# mikroAmpMeterV150_AnalogFrontend.net
KiCad netlist of a schematic drawn in EAGLE
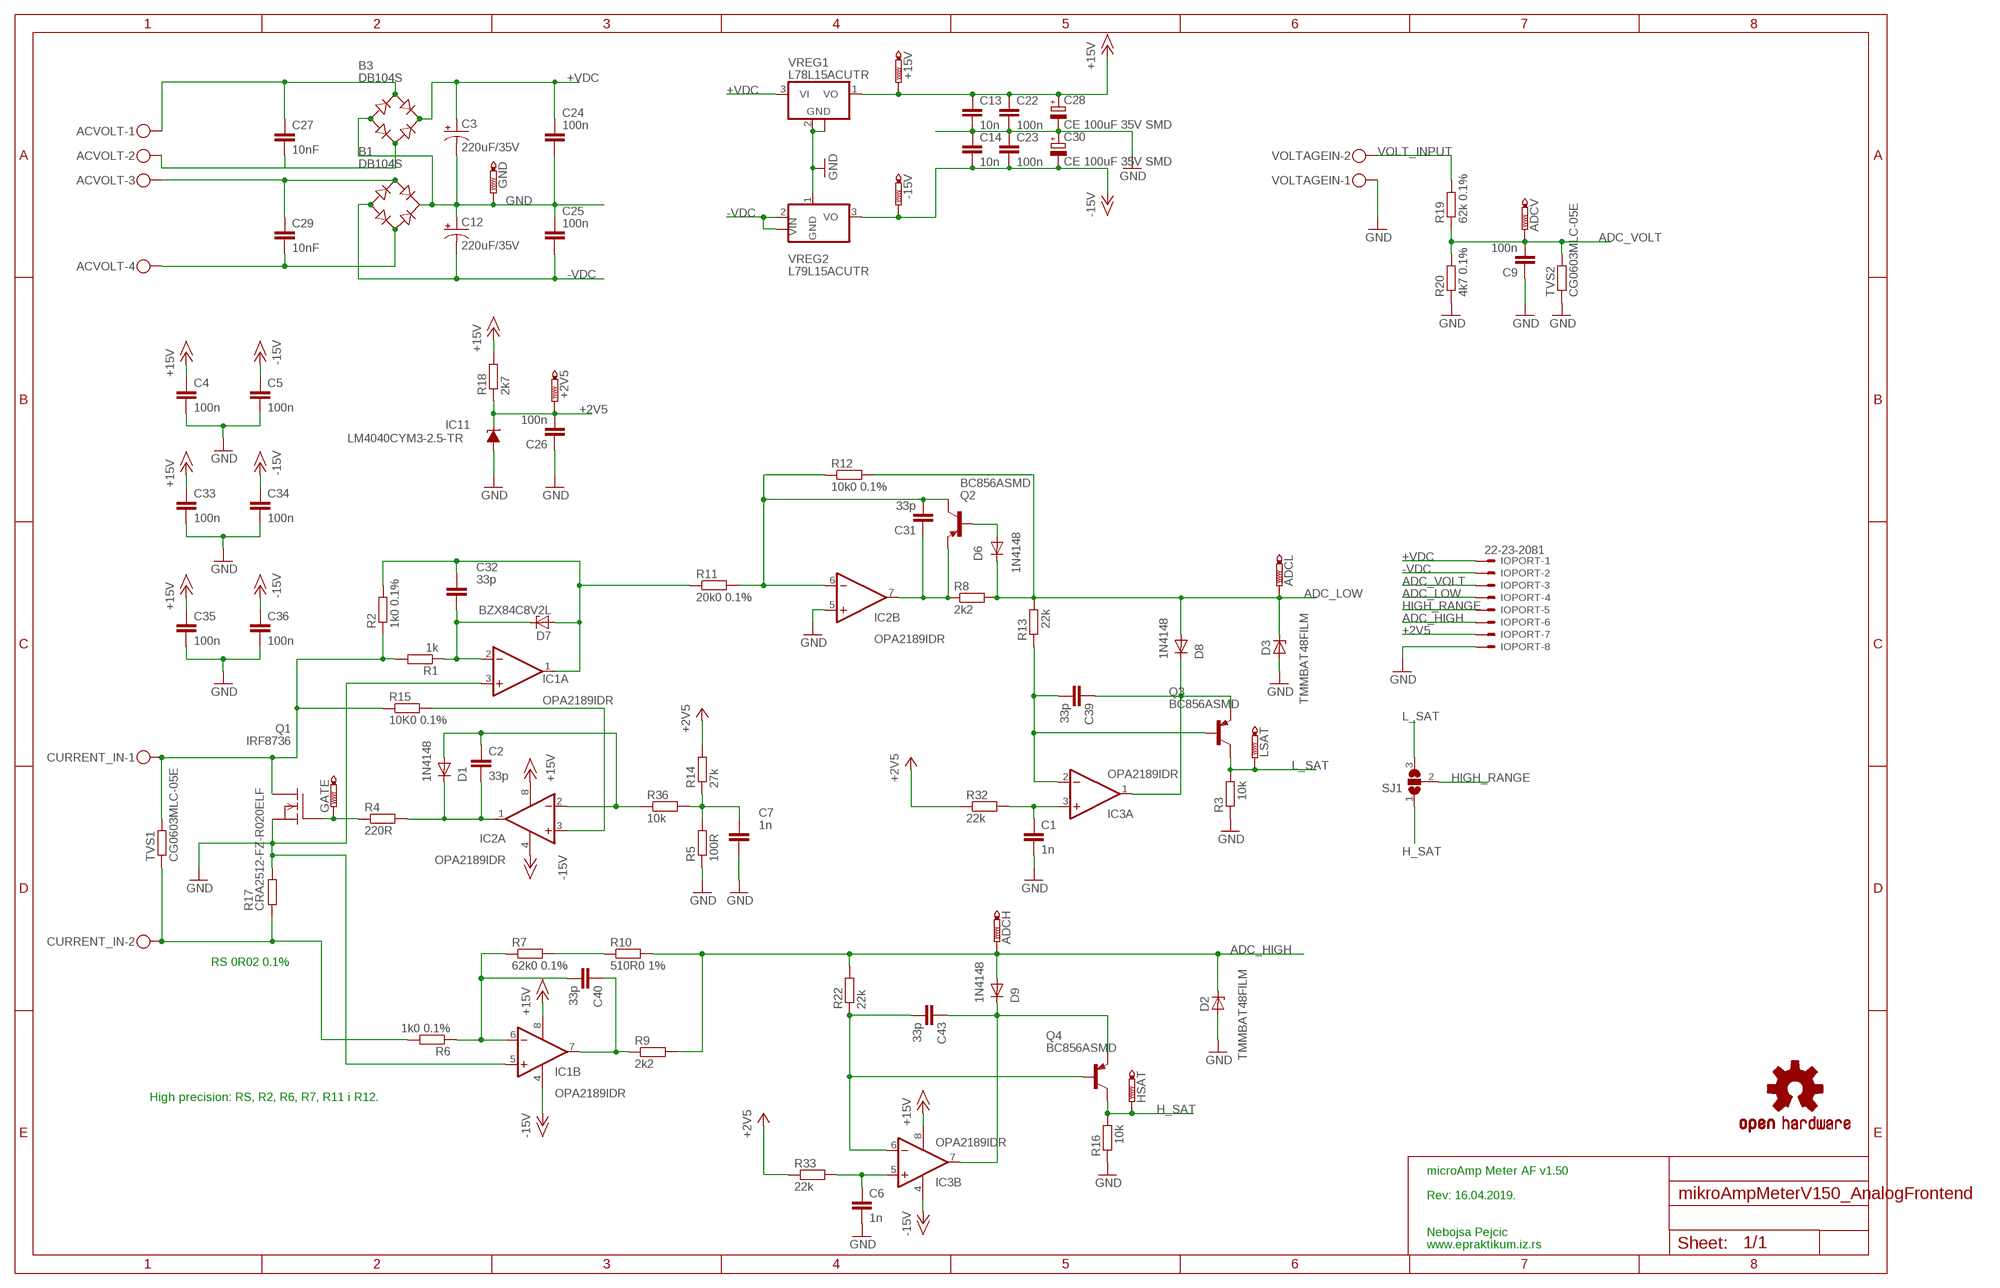
[diagram p0: schematic, sheet 1]

(export (version "E")
  (design (tool "Eeschema 10.0.6"))
  (components
    (comp (ref "+2V5")
      (value "PTR1TP15R")
      (footprint "eagle-import:TP15R")
      (libsource (lib "eagle-import") (part "PTR1TP15R"))
    )
    (comp (ref "+15V")
      (value "PTR1TP15R")
      (footprint "eagle-import:TP15R")
      (libsource (lib "eagle-import") (part "PTR1TP15R"))
    )
    (comp (ref "-15V")
      (value "PTR1TP15R")
      (footprint "eagle-import:TP15R")
      (libsource (lib "eagle-import") (part "PTR1TP15R"))
    )
    (comp (ref "ACVOLT")
      (value "MKDSN1,5/4-5,08")
      (footprint "eagle-import:MKDSN1,5_4-5,08")
      (fields (field (name "MPN") "SMKDSN1,5/4-5,08"))
      (libsource (lib "eagle-import") (part "MKDSN1,5/4-5,08"))
    )
    (comp (ref "ADCH")
      (value "PTR1TP15R")
      (footprint "eagle-import:TP15R")
      (libsource (lib "eagle-import") (part "PTR1TP15R"))
    )
    (comp (ref "ADCL")
      (value "PTR1TP15R")
      (footprint "eagle-import:TP15R")
      (libsource (lib "eagle-import") (part "PTR1TP15R"))
    )
    (comp (ref "ADCV")
      (value "PTR1TP15R")
      (footprint "eagle-import:TP15R")
      (libsource (lib "eagle-import") (part "PTR1TP15R"))
    )
    (comp (ref "B1")
      (value "DB104S")
      (footprint "eagle-import:DBS")
      (libsource (lib "eagle-import") (part "DB?GLS204"))
    )
    (comp (ref "B3")
      (value "DB104S")
      (footprint "eagle-import:DBS")
      (libsource (lib "eagle-import") (part "DB?GLS204"))
    )
    (comp (ref "C1")
      (value "1n")
      (footprint "eagle-import:C0805")
      (libsource (lib "eagle-import") (part "C-EUC0805"))
    )
    (comp (ref "C2")
      (value "33p")
      (footprint "eagle-import:C0805")
      (libsource (lib "eagle-import") (part "C-EUC0805"))
    )
    (comp (ref "C3")
      (value "220uF/35V")
      (footprint "eagle-import:153CLV-1014")
      (libsource (lib "eagle-import") (part "CPOL-US153CLV-1014"))
    )
    (comp (ref "C4")
      (value "100n")
      (footprint "eagle-import:C0805")
      (libsource (lib "eagle-import") (part "C-EUC0805"))
    )
    (comp (ref "C5")
      (value "100n")
      (footprint "eagle-import:C0805")
      (libsource (lib "eagle-import") (part "C-EUC0805"))
    )
    (comp (ref "C6")
      (value "1n")
      (footprint "eagle-import:C0805")
      (libsource (lib "eagle-import") (part "C-EUC0805"))
    )
    (comp (ref "C7")
      (value "1n")
      (footprint "eagle-import:C0805")
      (libsource (lib "eagle-import") (part "C-EUC0805"))
    )
    (comp (ref "C9")
      (value "100n")
      (footprint "eagle-import:C0805")
      (libsource (lib "eagle-import") (part "C-EUC0805"))
    )
    (comp (ref "C12")
      (value "220uF/35V")
      (footprint "eagle-import:153CLV-1014")
      (libsource (lib "eagle-import") (part "CPOL-US153CLV-1014"))
    )
    (comp (ref "C13")
      (value "10n")
      (footprint "eagle-import:C0805")
      (libsource (lib "eagle-import") (part "C-EUC0805"))
    )
    (comp (ref "C14")
      (value "10n")
      (footprint "eagle-import:C0805")
      (libsource (lib "eagle-import") (part "C-EUC0805"))
    )
    (comp (ref "C22")
      (value "100n")
      (footprint "eagle-import:C0805")
      (libsource (lib "eagle-import") (part "C-EUC0805"))
    )
    (comp (ref "C23")
      (value "100n")
      (footprint "eagle-import:C0805")
      (libsource (lib "eagle-import") (part "C-EUC0805"))
    )
    (comp (ref "C24")
      (value "100n")
      (footprint "eagle-import:C0805")
      (libsource (lib "eagle-import") (part "C-EUC0805"))
    )
    (comp (ref "C25")
      (value "100n")
      (footprint "eagle-import:C0805")
      (libsource (lib "eagle-import") (part "C-EUC0805"))
    )
    (comp (ref "C26")
      (value "100n")
      (footprint "eagle-import:C0805")
      (libsource (lib "eagle-import") (part "C-EUC0805"))
    )
    (comp (ref "C27")
      (value "10nF")
      (footprint "eagle-import:C1206")
      (libsource (lib "eagle-import") (part "C-EUC1206"))
    )
    (comp (ref "C28")
      (value "CE 100uF 35V SMD")
      (footprint "eagle-import:UD-6,3X7,7_NICHICON")
      (libsource (lib "eagle-import") (part "CPOL-EUUD-6,3X7,7"))
    )
    (comp (ref "C29")
      (value "10nF")
      (footprint "eagle-import:C1206")
      (libsource (lib "eagle-import") (part "C-EUC1206"))
    )
    (comp (ref "C30")
      (value "CE 100uF 35V SMD")
      (footprint "eagle-import:UD-6,3X7,7_NICHICON")
      (libsource (lib "eagle-import") (part "CPOL-EUUD-6,3X7,7"))
    )
    (comp (ref "C31")
      (value "33p")
      (footprint "eagle-import:C0805")
      (libsource (lib "eagle-import") (part "C-EUC0805"))
    )
    (comp (ref "C32")
      (value "33p")
      (footprint "eagle-import:C0805")
      (libsource (lib "eagle-import") (part "C-EUC0805"))
    )
    (comp (ref "C33")
      (value "100n")
      (footprint "eagle-import:C0805")
      (libsource (lib "eagle-import") (part "C-EUC0805"))
    )
    (comp (ref "C34")
      (value "100n")
      (footprint "eagle-import:C0805")
      (libsource (lib "eagle-import") (part "C-EUC0805"))
    )
    (comp (ref "C35")
      (value "100n")
      (footprint "eagle-import:C0805")
      (libsource (lib "eagle-import") (part "C-EUC0805"))
    )
    (comp (ref "C36")
      (value "100n")
      (footprint "eagle-import:C0805")
      (libsource (lib "eagle-import") (part "C-EUC0805"))
    )
    (comp (ref "C39")
      (value "33p")
      (footprint "eagle-import:C0805")
      (libsource (lib "eagle-import") (part "C-EUC0805"))
    )
    (comp (ref "C40")
      (value "33p")
      (footprint "eagle-import:C0805")
      (libsource (lib "eagle-import") (part "C-EUC0805"))
    )
    (comp (ref "C43")
      (value "33p")
      (footprint "eagle-import:C0805")
      (libsource (lib "eagle-import") (part "C-EUC0805"))
    )
    (comp (ref "CURRENT_IN")
      (value "MKDSN1,5/2-5,08")
      (footprint "eagle-import:MKDSN1,5_2-5,08")
      (fields (field (name "MPN") "MKDSN 1,5/2-5.08"))
      (libsource (lib "eagle-import") (part "MKDSN1,5/2-5,08"))
    )
    (comp (ref "D1")
      (value "1N4148")
      (footprint "eagle-import:SOD80C")
      (libsource (lib "eagle-import") (part "DIODE-SOD80C"))
    )
    (comp (ref "D2")
      (value "TMMBAT48FILM")
      (footprint "eagle-import:SOD80C")
      (libsource (lib "eagle-import") (part "ZENER-DIODESOD80C"))
    )
    (comp (ref "D3")
      (value "TMMBAT48FILM")
      (footprint "eagle-import:SOD80C")
      (libsource (lib "eagle-import") (part "ZENER-DIODESOD80C"))
    )
    (comp (ref "D6")
      (value "1N4148")
      (footprint "eagle-import:SOD80C")
      (libsource (lib "eagle-import") (part "DIODE-SOD80C"))
    )
    (comp (ref "D7")
      (value "BZX84C8V2L")
      (footprint "eagle-import:SOD80C")
      (libsource (lib "eagle-import") (part "ZENER-DIODESOD80C"))
    )
    (comp (ref "D8")
      (value "1N4148")
      (footprint "eagle-import:SOD80C")
      (libsource (lib "eagle-import") (part "DIODE-SOD80C"))
    )
    (comp (ref "D9")
      (value "1N4148")
      (footprint "eagle-import:SOD80C")
      (libsource (lib "eagle-import") (part "DIODE-SOD80C"))
    )
    (comp (ref "GATE")
      (value "PTR1TP15R")
      (footprint "eagle-import:TP15R")
      (libsource (lib "eagle-import") (part "PTR1TP15R"))
    )
    (comp (ref "GND")
      (value "PTR1TP15R")
      (footprint "eagle-import:TP15R")
      (libsource (lib "eagle-import") (part "PTR1TP15R"))
    )
    (comp (ref "HSAT")
      (value "PTR1TP15R")
      (footprint "eagle-import:TP15R")
      (libsource (lib "eagle-import") (part "PTR1TP15R"))
    )
    (comp (ref "IC1")
      (value "OPA2189IDR")
      (footprint "eagle-import:SO08@1")
      (libsource (lib "eagle-import") (part "OPA222D7"))
    )
    (comp (ref "IC2")
      (value "OPA2189IDR")
      (footprint "eagle-import:SO08@1")
      (libsource (lib "eagle-import") (part "OPA222D7"))
    )
    (comp (ref "IC3")
      (value "OPA2189IDR")
      (footprint "eagle-import:SO08@1")
      (libsource (lib "eagle-import") (part "OPA222D7"))
    )
    (comp (ref "IC11")
      (value "LM4040CYM3-2.5-TR")
      (footprint "eagle-import:DBZ_R-PDSO-G3")
      (fields (field (name "MPN") "LM4041A12IDBZR"))
      (libsource (lib "eagle-import") (part "LM4041DBZA12"))
    )
    (comp (ref "IOPORT")
      (value "22-23-2081")
      (footprint "eagle-import:22-23-2081")
      (fields (field (name "MF") "MOLEX"))
      (libsource (lib "eagle-import") (part "22-23-2081"))
    )
    (comp (ref "LOGO1")
      (value "OSHW-LOGOM")
      (footprint "eagle-import:OSHW-LOGO-M")
      (libsource (lib "eagle-import") (part "OSHW-LOGOM"))
    )
    (comp (ref "LSAT")
      (value "PTR1TP15R")
      (footprint "eagle-import:TP15R")
      (libsource (lib "eagle-import") (part "PTR1TP15R"))
    )
    (comp (ref "Q1")
      (value "IRF8736")
      (footprint "eagle-import:SO-8")
      (libsource (lib "eagle-import") (part "FDS5680"))
    )
    (comp (ref "Q2")
      (value "BC856ASMD")
      (footprint "eagle-import:SOT23-BEC")
      (libsource (lib "eagle-import") (part "BC856SMDA"))
    )
    (comp (ref "Q3")
      (value "BC856ASMD")
      (footprint "eagle-import:SOT23-BEC")
      (libsource (lib "eagle-import") (part "BC856SMDA"))
    )
    (comp (ref "Q4")
      (value "BC856ASMD")
      (footprint "eagle-import:SOT23-BEC")
      (libsource (lib "eagle-import") (part "BC856SMDA"))
    )
    (comp (ref "R1")
      (value "1k")
      (footprint "eagle-import:R0805")
      (libsource (lib "eagle-import") (part "R-EU_R0805"))
    )
    (comp (ref "R2")
      (value "1k0 0.1%")
      (footprint "eagle-import:R0805")
      (libsource (lib "eagle-import") (part "R-EU_R0805"))
    )
    (comp (ref "R3")
      (value "10k")
      (footprint "eagle-import:R0805")
      (libsource (lib "eagle-import") (part "R-EU_R0805"))
    )
    (comp (ref "R4")
      (value "220R")
      (footprint "eagle-import:R0805")
      (libsource (lib "eagle-import") (part "R-EU_R0805"))
    )
    (comp (ref "R5")
      (value "100R")
      (footprint "eagle-import:R0805")
      (libsource (lib "eagle-import") (part "R-EU_R0805"))
    )
    (comp (ref "R6")
      (value "1k0 0.1%")
      (footprint "eagle-import:R0805")
      (libsource (lib "eagle-import") (part "R-EU_R0805"))
    )
    (comp (ref "R7")
      (value "62k0 0.1%")
      (footprint "eagle-import:R0805")
      (libsource (lib "eagle-import") (part "R-EU_R0805"))
    )
    (comp (ref "R8")
      (value "2k2")
      (footprint "eagle-import:R0805")
      (libsource (lib "eagle-import") (part "R-EU_R0805"))
    )
    (comp (ref "R9")
      (value "2k2")
      (footprint "eagle-import:R0805")
      (libsource (lib "eagle-import") (part "R-EU_R0805"))
    )
    (comp (ref "R10")
      (value "510R0 1%")
      (footprint "eagle-import:R0805")
      (libsource (lib "eagle-import") (part "R-EU_R0805"))
    )
    (comp (ref "R11")
      (value "20k0 0.1%")
      (footprint "eagle-import:R0805")
      (libsource (lib "eagle-import") (part "R-EU_R0805"))
    )
    (comp (ref "R12")
      (value "10k0 0.1%")
      (footprint "eagle-import:R0805")
      (libsource (lib "eagle-import") (part "R-EU_R0805"))
    )
    (comp (ref "R13")
      (value "22k")
      (footprint "eagle-import:R0805")
      (libsource (lib "eagle-import") (part "R-EU_R0805"))
    )
    (comp (ref "R14")
      (value "27k")
      (footprint "eagle-import:R0805")
      (libsource (lib "eagle-import") (part "R-EU_R0805"))
    )
    (comp (ref "R15")
      (value "10K0 0.1%")
      (footprint "eagle-import:R0805")
      (libsource (lib "eagle-import") (part "R-EU_R0805"))
    )
    (comp (ref "R16")
      (value "10k")
      (footprint "eagle-import:R0805")
      (libsource (lib "eagle-import") (part "R-EU_R0805"))
    )
    (comp (ref "R17")
      (value "CRA2512-FZ-R020ELF")
      (footprint "eagle-import:R2512")
      (libsource (lib "eagle-import") (part "R-EU_R2512"))
    )
    (comp (ref "R18")
      (value "2k7")
      (footprint "eagle-import:R0805")
      (libsource (lib "eagle-import") (part "R-EU_R0805"))
    )
    (comp (ref "R19")
      (value "62k 0.1%")
      (footprint "eagle-import:R0805")
      (libsource (lib "eagle-import") (part "R-EU_R0805"))
    )
    (comp (ref "R20")
      (value "4k7 0.1%")
      (footprint "eagle-import:R0805")
      (libsource (lib "eagle-import") (part "R-EU_R0805"))
    )
    (comp (ref "R22")
      (value "22k")
      (footprint "eagle-import:R0805")
      (libsource (lib "eagle-import") (part "R-EU_R0805"))
    )
    (comp (ref "R32")
      (value "22k")
      (footprint "eagle-import:R0805")
      (libsource (lib "eagle-import") (part "R-EU_R0805"))
    )
    (comp (ref "R33")
      (value "22k")
      (footprint "eagle-import:R0805")
      (libsource (lib "eagle-import") (part "R-EU_R0805"))
    )
    (comp (ref "R36")
      (value "10k")
      (footprint "eagle-import:R0805")
      (libsource (lib "eagle-import") (part "R-EU_R0805"))
    )
    (comp (ref "SJ1")
      (value "SJ2W")
      (footprint "eagle-import:SJ_2")
      (libsource (lib "eagle-import") (part "SJ2W"))
    )
    (comp (ref "TVS1")
      (value "CG0603MLC-05E")
      (footprint "eagle-import:R0805")
      (libsource (lib "eagle-import") (part "R-EU_R0805"))
    )
    (comp (ref "TVS2")
      (value "CG0603MLC-05E")
      (footprint "eagle-import:R0805")
      (libsource (lib "eagle-import") (part "R-EU_R0805"))
    )
    (comp (ref "VOLTAGEIN")
      (value "MKDSN1,5/2-5,08")
      (footprint "eagle-import:MKDSN1,5_2-5,08")
      (fields
        (field (name "MPN") "MKDSN 1,5/2-5.08")
        (field (name "MPN_1") "MKDSN 1,5/2-5.08")
        (field (name "OC_FARNELL") "1792903")
        (field (name "OC_NEWARK") "30M2397")
      )
      (libsource (lib "eagle-import") (part "MKDSN1,5/2-5,08"))
    )
    (comp (ref "VREG1")
      (value "L78L15ACUTR")
      (footprint "eagle-import:SOT89")
      (libsource (lib "eagle-import") (part "78LF05"))
    )
    (comp (ref "VREG2")
      (value "L79L15ACUTR")
      (footprint "eagle-import:SOT89")
      (libsource (lib "eagle-import") (part "L79L15ACUTR"))
    )
  )
  (nets
    (net (code "1") (name "+2V5") (class "Default")
      (node (ref "+2V5") (pin "TP") (pinfunction "TP_TP") (pintype "input"))
      (node (ref "C26") (pin "2") (pinfunction "2_2") (pintype "passive"))
      (node (ref "IC11") (pin "1") (pinfunction "C_1") (pintype "passive"))
      (node (ref "IOPORT") (pin "7") (pinfunction "S_7") (pintype "passive"))
      (node (ref "R14") (pin "2") (pinfunction "2_2") (pintype "passive"))
      (node (ref "R18") (pin "1") (pinfunction "1_1") (pintype "passive"))
      (node (ref "R32") (pin "1") (pinfunction "1_1") (pintype "passive"))
      (node (ref "R33") (pin "1") (pinfunction "1_1") (pintype "passive"))
    )
    (net (code "2") (name "+15V") (class "Default")
      (node (ref "+15V") (pin "TP") (pinfunction "TP_TP") (pintype "input"))
      (node (ref "C13") (pin "1") (pinfunction "1_1") (pintype "passive"))
      (node (ref "C22") (pin "1") (pinfunction "1_1") (pintype "passive"))
      (node (ref "C28") (pin "+") (pinfunction "+_+") (pintype "passive"))
      (node (ref "C33") (pin "1") (pinfunction "1_1") (pintype "passive"))
      (node (ref "C35") (pin "1") (pinfunction "1_1") (pintype "passive"))
      (node (ref "C4") (pin "1") (pinfunction "1_1") (pintype "passive"))
      (node (ref "IC1") (pin "8") (pinfunction "V+_8") (pintype "power_in"))
      (node (ref "IC2") (pin "8") (pinfunction "V+_8") (pintype "power_in"))
      (node (ref "IC3") (pin "8") (pinfunction "V+_8") (pintype "power_in"))
      (node (ref "R18") (pin "2") (pinfunction "2_2") (pintype "passive"))
      (node (ref "VREG1") (pin "1") (pinfunction "VO_1") (pintype "passive"))
    )
    (net (code "3") (name "-15V") (class "Default")
      (node (ref "-15V") (pin "TP") (pinfunction "TP_TP") (pintype "input"))
      (node (ref "C14") (pin "2") (pinfunction "2_2") (pintype "passive"))
      (node (ref "C23") (pin "2") (pinfunction "2_2") (pintype "passive"))
      (node (ref "C30") (pin "-") (pinfunction "-_-") (pintype "passive"))
      (node (ref "C34") (pin "1") (pinfunction "1_1") (pintype "passive"))
      (node (ref "C36") (pin "1") (pinfunction "1_1") (pintype "passive"))
      (node (ref "C5") (pin "1") (pinfunction "1_1") (pintype "passive"))
      (node (ref "IC1") (pin "4") (pinfunction "V-_4") (pintype "power_in"))
      (node (ref "IC2") (pin "4") (pinfunction "V-_4") (pintype "power_in"))
      (node (ref "IC3") (pin "4") (pinfunction "V-_4") (pintype "power_in"))
      (node (ref "VREG2") (pin "3") (pinfunction "VO_3") (pintype "passive"))
    )
    (net (code "4") (name "/+VDC") (class "Default")
      (node (ref "B3") (pin "+") (pinfunction "+_+") (pintype "passive"))
      (node (ref "C24") (pin "2") (pinfunction "2_2") (pintype "passive"))
      (node (ref "C3") (pin "+") (pinfunction "+_+") (pintype "passive"))
      (node (ref "IOPORT") (pin "1") (pinfunction "S_1") (pintype "passive"))
      (node (ref "VREG1") (pin "3") (pinfunction "VI_3") (pintype "input"))
    )
    (net (code "5") (name "/-VDC") (class "Default")
      (node (ref "B1") (pin "-") (pinfunction "-_-") (pintype "passive"))
      (node (ref "C12") (pin "-") (pinfunction "-_-") (pintype "passive"))
      (node (ref "C25") (pin "1") (pinfunction "1_1") (pintype "passive"))
      (node (ref "IOPORT") (pin "2") (pinfunction "S_2") (pintype "passive"))
      (node (ref "VREG2") (pin "2") (pinfunction "VIN_2") (pintype "passive"))
      (node (ref "VREG2") (pin "2@1") (pinfunction "VIN_2@1") (pintype "passive"))
    )
    (net (code "6") (name "/ADC_HIGH") (class "Default")
      (node (ref "ADCH") (pin "TP") (pinfunction "TP_TP") (pintype "input"))
      (node (ref "D2") (pin "C") (pinfunction "C_C") (pintype "passive"))
      (node (ref "D9") (pin "A") (pinfunction "A_A") (pintype "passive"))
      (node (ref "IOPORT") (pin "6") (pinfunction "S_6") (pintype "passive"))
      (node (ref "R10") (pin "2") (pinfunction "2_2") (pintype "passive"))
      (node (ref "R22") (pin "2") (pinfunction "2_2") (pintype "passive"))
      (node (ref "R9") (pin "2") (pinfunction "2_2") (pintype "passive"))
    )
    (net (code "7") (name "/ADC_LOW") (class "Default")
      (node (ref "ADCL") (pin "TP") (pinfunction "TP_TP") (pintype "input"))
      (node (ref "D3") (pin "C") (pinfunction "C_C") (pintype "passive"))
      (node (ref "D6") (pin "C") (pinfunction "C_C") (pintype "passive"))
      (node (ref "D8") (pin "A") (pinfunction "A_A") (pintype "passive"))
      (node (ref "IOPORT") (pin "4") (pinfunction "S_4") (pintype "passive"))
      (node (ref "R12") (pin "2") (pinfunction "2_2") (pintype "passive"))
      (node (ref "R13") (pin "2") (pinfunction "2_2") (pintype "passive"))
      (node (ref "R8") (pin "2") (pinfunction "2_2") (pintype "passive"))
    )
    (net (code "8") (name "/ADC_VOLT") (class "Default")
      (node (ref "ADCV") (pin "TP") (pinfunction "TP_TP") (pintype "input"))
      (node (ref "C9") (pin "2") (pinfunction "2_2") (pintype "passive"))
      (node (ref "IOPORT") (pin "3") (pinfunction "S_3") (pintype "passive"))
      (node (ref "R19") (pin "1") (pinfunction "1_1") (pintype "passive"))
      (node (ref "R20") (pin "2") (pinfunction "2_2") (pintype "passive"))
      (node (ref "TVS2") (pin "2") (pinfunction "2_2") (pintype "passive"))
    )
    (net (code "9") (name "/HIGH_RANGE") (class "Default")
      (node (ref "IOPORT") (pin "5") (pinfunction "S_5") (pintype "passive"))
      (node (ref "SJ1") (pin "2") (pinfunction "2_2") (pintype "passive"))
    )
    (net (code "10") (name "/H_SAT") (class "Default")
      (node (ref "HSAT") (pin "TP") (pinfunction "TP_TP") (pintype "input"))
      (node (ref "Q4") (pin "C") (pinfunction "C_C") (pintype "passive"))
      (node (ref "R16") (pin "2") (pinfunction "2_2") (pintype "passive"))
      (node (ref "SJ1") (pin "1") (pinfunction "1_1") (pintype "passive"))
    )
    (net (code "11") (name "/L_SAT") (class "Default")
      (node (ref "LSAT") (pin "TP") (pinfunction "TP_TP") (pintype "input"))
      (node (ref "Q3") (pin "C") (pinfunction "C_C") (pintype "passive"))
      (node (ref "R3") (pin "2") (pinfunction "2_2") (pintype "passive"))
      (node (ref "SJ1") (pin "3") (pinfunction "3_3") (pintype "passive"))
    )
    (net (code "12") (name "/VOLT_INPUT") (class "Default")
      (node (ref "R19") (pin "2") (pinfunction "2_2") (pintype "passive"))
      (node (ref "VOLTAGEIN") (pin "2") (pinfunction "KL_2") (pintype "passive"))
    )
    (net (code "13") (name "GND") (class "Default")
      (node (ref "B1") (pin "+") (pinfunction "+_+") (pintype "passive"))
      (node (ref "B3") (pin "-") (pinfunction "-_-") (pintype "passive"))
      (node (ref "C1") (pin "2") (pinfunction "2_2") (pintype "passive"))
      (node (ref "C12") (pin "+") (pinfunction "+_+") (pintype "passive"))
      (node (ref "C13") (pin "2") (pinfunction "2_2") (pintype "passive"))
      (node (ref "C14") (pin "1") (pinfunction "1_1") (pintype "passive"))
      (node (ref "C22") (pin "2") (pinfunction "2_2") (pintype "passive"))
      (node (ref "C23") (pin "1") (pinfunction "1_1") (pintype "passive"))
      (node (ref "C24") (pin "1") (pinfunction "1_1") (pintype "passive"))
      (node (ref "C25") (pin "2") (pinfunction "2_2") (pintype "passive"))
      (node (ref "C26") (pin "1") (pinfunction "1_1") (pintype "passive"))
      (node (ref "C28") (pin "-") (pinfunction "-_-") (pintype "passive"))
      (node (ref "C3") (pin "-") (pinfunction "-_-") (pintype "passive"))
      (node (ref "C30") (pin "+") (pinfunction "+_+") (pintype "passive"))
      (node (ref "C33") (pin "2") (pinfunction "2_2") (pintype "passive"))
      (node (ref "C34") (pin "2") (pinfunction "2_2") (pintype "passive"))
      (node (ref "C35") (pin "2") (pinfunction "2_2") (pintype "passive"))
      (node (ref "C36") (pin "2") (pinfunction "2_2") (pintype "passive"))
      (node (ref "C4") (pin "2") (pinfunction "2_2") (pintype "passive"))
      (node (ref "C5") (pin "2") (pinfunction "2_2") (pintype "passive"))
      (node (ref "C6") (pin "2") (pinfunction "2_2") (pintype "passive"))
      (node (ref "C7") (pin "2") (pinfunction "2_2") (pintype "passive"))
      (node (ref "C9") (pin "1") (pinfunction "1_1") (pintype "passive"))
      (node (ref "D2") (pin "A") (pinfunction "A_A") (pintype "passive"))
      (node (ref "D3") (pin "A") (pinfunction "A_A") (pintype "passive"))
      (node (ref "GND") (pin "TP") (pinfunction "TP_TP") (pintype "input"))
      (node (ref "IC1") (pin "3") (pinfunction "+IN_3") (pintype "input"))
      (node (ref "IC1") (pin "5") (pinfunction "+IN_5") (pintype "input"))
      (node (ref "IC11") (pin "2") (pinfunction "A_2") (pintype "passive"))
      (node (ref "IC2") (pin "5") (pinfunction "+IN_5") (pintype "input"))
      (node (ref "IOPORT") (pin "8") (pinfunction "S_8") (pintype "passive"))
      (node (ref "Q1") (pin "1") (pinfunction "S_1") (pintype "passive"))
      (node (ref "Q1") (pin "2") (pinfunction "S_2") (pintype "passive"))
      (node (ref "Q1") (pin "3") (pinfunction "S_3") (pintype "passive"))
      (node (ref "R16") (pin "1") (pinfunction "1_1") (pintype "passive"))
      (node (ref "R17") (pin "2") (pinfunction "2_2") (pintype "passive"))
      (node (ref "R20") (pin "1") (pinfunction "1_1") (pintype "passive"))
      (node (ref "R3") (pin "1") (pinfunction "1_1") (pintype "passive"))
      (node (ref "R5") (pin "1") (pinfunction "1_1") (pintype "passive"))
      (node (ref "TVS2") (pin "1") (pinfunction "1_1") (pintype "passive"))
      (node (ref "VOLTAGEIN") (pin "1") (pinfunction "KL_1") (pintype "passive"))
      (node (ref "VREG1") (pin "2") (pinfunction "GND_2") (pintype "passive"))
      (node (ref "VREG1") (pin "2@1") (pinfunction "GND_2@1") (pintype "passive"))
      (node (ref "VREG2") (pin "1") (pinfunction "GND_1") (pintype "input"))
    )
    (net (code "14") (name "Net-(ACVOLTA-KL)") (class "Default")
      (node (ref "ACVOLT") (pin "1") (pinfunction "KL_1") (pintype "passive"))
      (node (ref "B3") (pin "AC1") (pinfunction "AC1_AC1") (pintype "passive"))
      (node (ref "C27") (pin "2") (pinfunction "2_2") (pintype "passive"))
    )
    (net (code "15") (name "Net-(ACVOLTB-KL)") (class "Default")
      (node (ref "ACVOLT") (pin "2") (pinfunction "KL_2") (pintype "passive"))
      (node (ref "B3") (pin "AC2") (pinfunction "AC2_AC2") (pintype "passive"))
      (node (ref "C27") (pin "1") (pinfunction "1_1") (pintype "passive"))
    )
    (net (code "16") (name "Net-(ACVOLTC-KL)") (class "Default")
      (node (ref "ACVOLT") (pin "3") (pinfunction "KL_3") (pintype "passive"))
      (node (ref "B1") (pin "AC1") (pinfunction "AC1_AC1") (pintype "passive"))
      (node (ref "C29") (pin "2") (pinfunction "2_2") (pintype "passive"))
    )
    (net (code "17") (name "Net-(ACVOLTD-KL)") (class "Default")
      (node (ref "ACVOLT") (pin "4") (pinfunction "KL_4") (pintype "passive"))
      (node (ref "B1") (pin "AC2") (pinfunction "AC2_AC2") (pintype "passive"))
      (node (ref "C29") (pin "1") (pinfunction "1_1") (pintype "passive"))
    )
    (net (code "18") (name "Net-(C7-Pad1)") (class "Default")
      (node (ref "C7") (pin "1") (pinfunction "1_1") (pintype "passive"))
      (node (ref "R14") (pin "1") (pinfunction "1_1") (pintype "passive"))
      (node (ref "R36") (pin "2") (pinfunction "2_2") (pintype "passive"))
      (node (ref "R5") (pin "2") (pinfunction "2_2") (pintype "passive"))
    )
    (net (code "19") (name "Net-(CURRENT_INA-KL)") (class "Default")
      (node (ref "CURRENT_IN") (pin "1") (pinfunction "KL_1") (pintype "passive"))
      (node (ref "Q1") (pin "5") (pinfunction "D_5") (pintype "passive"))
      (node (ref "Q1") (pin "6") (pinfunction "D_6") (pintype "passive"))
      (node (ref "Q1") (pin "7") (pinfunction "D_7") (pintype "passive"))
      (node (ref "Q1") (pin "8") (pinfunction "D_8") (pintype "passive"))
      (node (ref "R1") (pin "2") (pinfunction "2_2") (pintype "passive"))
      (node (ref "R15") (pin "1") (pinfunction "1_1") (pintype "passive"))
      (node (ref "R2") (pin "1") (pinfunction "1_1") (pintype "passive"))
      (node (ref "TVS1") (pin "2") (pinfunction "2_2") (pintype "passive"))
    )
    (net (code "20") (name "Net-(CURRENT_INB-KL)") (class "Default")
      (node (ref "CURRENT_IN") (pin "2") (pinfunction "KL_2") (pintype "passive"))
      (node (ref "R17") (pin "1") (pinfunction "1_1") (pintype "passive"))
      (node (ref "R6") (pin "2") (pinfunction "2_2") (pintype "passive"))
      (node (ref "TVS1") (pin "1") (pinfunction "1_1") (pintype "passive"))
    )
    (net (code "21") (name "Net-(D6-PadA)") (class "Default")
      (node (ref "D6") (pin "A") (pinfunction "A_A") (pintype "passive"))
      (node (ref "Q2") (pin "B") (pinfunction "B_B") (pintype "passive"))
    )
    (net (code "22") (name "Net-(IC1A--IN)") (class "Default")
      (node (ref "C32") (pin "2") (pinfunction "2_2") (pintype "passive"))
      (node (ref "D7") (pin "C") (pinfunction "C_C") (pintype "passive"))
      (node (ref "IC1") (pin "2") (pinfunction "-IN_2") (pintype "input"))
      (node (ref "R1") (pin "1") (pinfunction "1_1") (pintype "passive"))
    )
    (net (code "23") (name "Net-(IC1A-OUT)") (class "Default")
      (node (ref "C32") (pin "1") (pinfunction "1_1") (pintype "passive"))
      (node (ref "D7") (pin "A") (pinfunction "A_A") (pintype "passive"))
      (node (ref "IC1") (pin "1") (pinfunction "OUT_1") (pintype "output"))
      (node (ref "R11") (pin "1") (pinfunction "1_1") (pintype "passive"))
      (node (ref "R2") (pin "2") (pinfunction "2_2") (pintype "passive"))
    )
    (net (code "24") (name "Net-(IC1B--IN)") (class "Default")
      (node (ref "C40") (pin "2") (pinfunction "2_2") (pintype "passive"))
      (node (ref "IC1") (pin "6") (pinfunction "-IN_6") (pintype "input"))
      (node (ref "R6") (pin "1") (pinfunction "1_1") (pintype "passive"))
      (node (ref "R7") (pin "1") (pinfunction "1_1") (pintype "passive"))
    )
    (net (code "25") (name "Net-(IC1B-OUT)") (class "Default")
      (node (ref "C40") (pin "1") (pinfunction "1_1") (pintype "passive"))
      (node (ref "IC1") (pin "7") (pinfunction "OUT_7") (pintype "output"))
      (node (ref "R9") (pin "1") (pinfunction "1_1") (pintype "passive"))
    )
    (net (code "26") (name "Net-(IC2A-+IN)") (class "Default")
      (node (ref "IC2") (pin "3") (pinfunction "+IN_3") (pintype "input"))
      (node (ref "R15") (pin "2") (pinfunction "2_2") (pintype "passive"))
    )
    (net (code "27") (name "Net-(IC2A--IN)") (class "Default")
      (node (ref "C2") (pin "1") (pinfunction "1_1") (pintype "passive"))
      (node (ref "D1") (pin "A") (pinfunction "A_A") (pintype "passive"))
      (node (ref "IC2") (pin "2") (pinfunction "-IN_2") (pintype "input"))
      (node (ref "R36") (pin "1") (pinfunction "1_1") (pintype "passive"))
    )
    (net (code "28") (name "Net-(IC2A-OUT)") (class "Default")
      (node (ref "C2") (pin "2") (pinfunction "2_2") (pintype "passive"))
      (node (ref "D1") (pin "C") (pinfunction "C_C") (pintype "passive"))
      (node (ref "IC2") (pin "1") (pinfunction "OUT_1") (pintype "output"))
      (node (ref "R4") (pin "2") (pinfunction "2_2") (pintype "passive"))
    )
    (net (code "29") (name "Net-(IC2B--IN)") (class "Default")
      (node (ref "C31") (pin "2") (pinfunction "2_2") (pintype "passive"))
      (node (ref "IC2") (pin "6") (pinfunction "-IN_6") (pintype "input"))
      (node (ref "Q2") (pin "C") (pinfunction "C_C") (pintype "passive"))
      (node (ref "R11") (pin "2") (pinfunction "2_2") (pintype "passive"))
      (node (ref "R12") (pin "1") (pinfunction "1_1") (pintype "passive"))
    )
    (net (code "30") (name "Net-(IC2B-OUT)") (class "Default")
      (node (ref "C31") (pin "1") (pinfunction "1_1") (pintype "passive"))
      (node (ref "IC2") (pin "7") (pinfunction "OUT_7") (pintype "output"))
      (node (ref "Q2") (pin "E") (pinfunction "E_E") (pintype "passive"))
      (node (ref "R8") (pin "1") (pinfunction "1_1") (pintype "passive"))
    )
    (net (code "31") (name "Net-(IC3A-+IN)") (class "Default")
      (node (ref "C1") (pin "1") (pinfunction "1_1") (pintype "passive"))
      (node (ref "IC3") (pin "3") (pinfunction "+IN_3") (pintype "input"))
      (node (ref "R32") (pin "2") (pinfunction "2_2") (pintype "passive"))
    )
    (net (code "32") (name "Net-(IC3A--IN)") (class "Default")
      (node (ref "C39") (pin "2") (pinfunction "2_2") (pintype "passive"))
      (node (ref "IC3") (pin "2") (pinfunction "-IN_2") (pintype "input"))
      (node (ref "Q3") (pin "B") (pinfunction "B_B") (pintype "passive"))
      (node (ref "R13") (pin "1") (pinfunction "1_1") (pintype "passive"))
    )
    (net (code "33") (name "Net-(IC3A-OUT)") (class "Default")
      (node (ref "C39") (pin "1") (pinfunction "1_1") (pintype "passive"))
      (node (ref "D8") (pin "C") (pinfunction "C_C") (pintype "passive"))
      (node (ref "IC3") (pin "1") (pinfunction "OUT_1") (pintype "output"))
      (node (ref "Q3") (pin "E") (pinfunction "E_E") (pintype "passive"))
    )
    (net (code "34") (name "Net-(IC3B-+IN)") (class "Default")
      (node (ref "C6") (pin "1") (pinfunction "1_1") (pintype "passive"))
      (node (ref "IC3") (pin "5") (pinfunction "+IN_5") (pintype "input"))
      (node (ref "R33") (pin "2") (pinfunction "2_2") (pintype "passive"))
    )
    (net (code "35") (name "Net-(IC3B--IN)") (class "Default")
      (node (ref "C43") (pin "2") (pinfunction "2_2") (pintype "passive"))
      (node (ref "IC3") (pin "6") (pinfunction "-IN_6") (pintype "input"))
      (node (ref "Q4") (pin "B") (pinfunction "B_B") (pintype "passive"))
      (node (ref "R22") (pin "1") (pinfunction "1_1") (pintype "passive"))
    )
    (net (code "36") (name "Net-(IC3B-OUT)") (class "Default")
      (node (ref "C43") (pin "1") (pinfunction "1_1") (pintype "passive"))
      (node (ref "D9") (pin "C") (pinfunction "C_C") (pintype "passive"))
      (node (ref "IC3") (pin "7") (pinfunction "OUT_7") (pintype "output"))
      (node (ref "Q4") (pin "E") (pinfunction "E_E") (pintype "passive"))
    )
    (net (code "37") (name "Net-(Q1-G)") (class "Default")
      (node (ref "GATE") (pin "TP") (pinfunction "TP_TP") (pintype "input"))
      (node (ref "Q1") (pin "4") (pinfunction "G_4") (pintype "passive"))
      (node (ref "R4") (pin "1") (pinfunction "1_1") (pintype "passive"))
    )
    (net (code "38") (name "Net-(R10-Pad1)") (class "Default")
      (node (ref "R10") (pin "1") (pinfunction "1_1") (pintype "passive"))
      (node (ref "R7") (pin "2") (pinfunction "2_2") (pintype "passive"))
    )
  )
)
